# LED_bargraph.net
KiCad netlist of a schematic drawn in Altium Designer
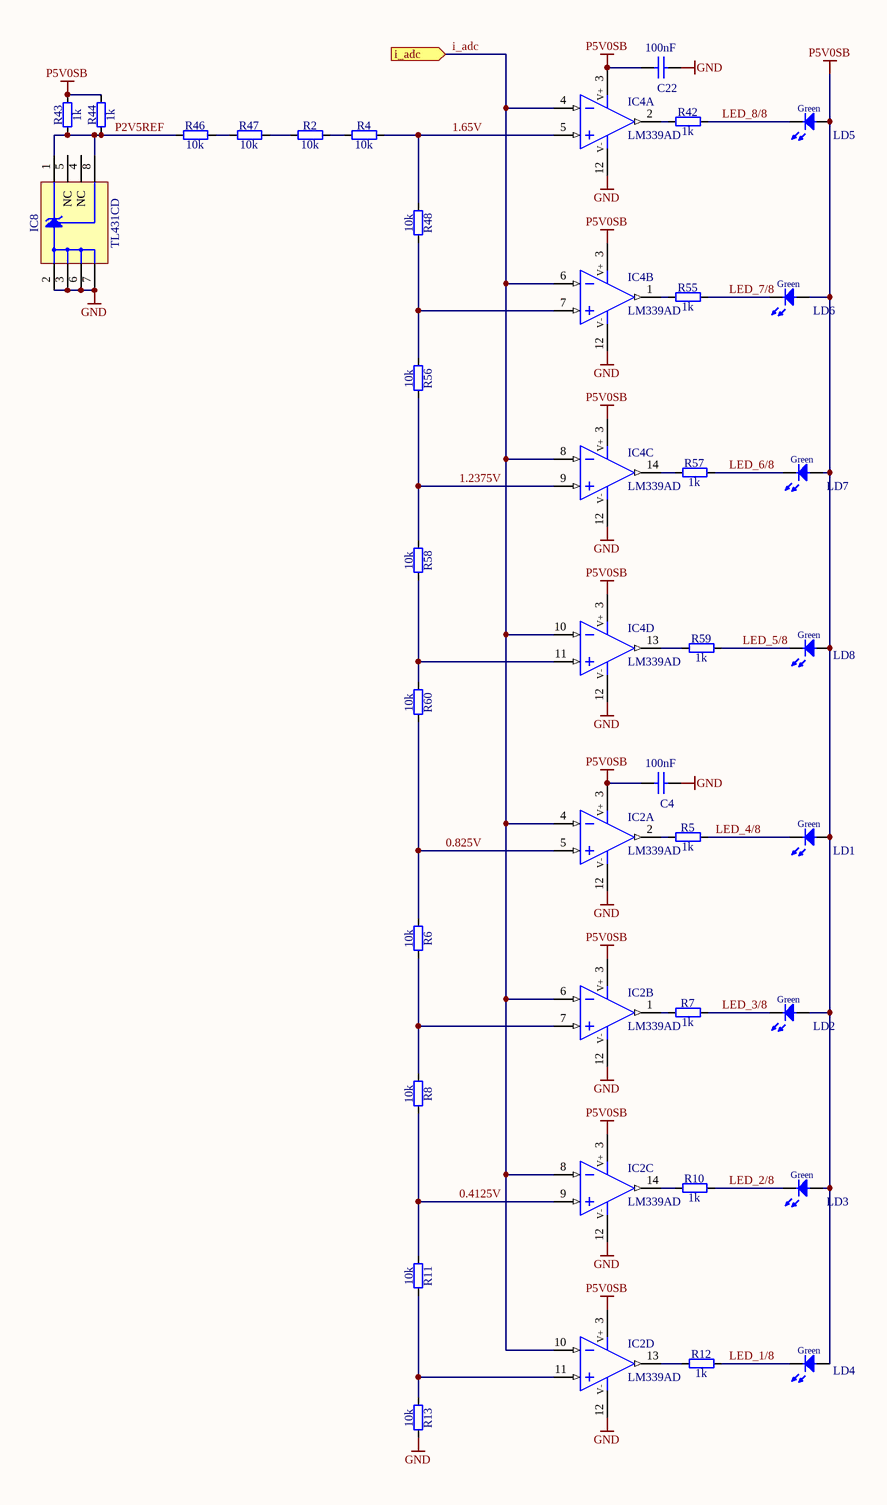
[diagram p0: LED_bargraph.SchDoc]

(export (version "E")
  (design (tool "Eeschema 10.0.6"))
  (components
    (comp (ref "C4")
      (value "100nF")
      (footprint "CAPC1005X55N")
      (description "Non-polarised capacitor")
      (fields
        (field (name "PART NUMBER") "CC0402_100NF_25V_10%_X7R_YUDEN_TMK105B7104KVHF")
        (field (name "VOLTAGE") "25V")
        (field (name "AUTHOR") "CERN DEM JLC")
      )
      (libsource (lib "Capacitors") (part "Capacitor - non polarized"))
    )
    (comp (ref "C22")
      (value "100nF")
      (footprint "CAPC1005X55N")
      (description "Non-polarised capacitor")
      (fields
        (field (name "PART NUMBER") "CC0402_100NF_25V_10%_X7R_YUDEN_TMK105B7104KVHF")
        (field (name "VOLTAGE") "25V")
        (field (name "AUTHOR") "CERN DEM JLC")
      )
      (libsource (lib "Capacitors") (part "Capacitor - non polarized"))
    )
    (comp (ref "IC2")
      (value "LM339AD")
      (footprint "SOIC127P600X175-14N")
      (description "Quad Operational Amplifier")
      (fields (field (name "MANUFACTURER") "TEXAS INSTRUMENTS") (field (name "AUTHOR") "CERN DEM JLC"))
      (libsource (lib "ICs And Semiconductors") (part "Operational Amplifier x4 Type2"))
    )
    (comp (ref "IC4")
      (value "LM339AD")
      (footprint "SOIC127P600X175-14N")
      (description "Quad Operational Amplifier")
      (fields (field (name "MANUFACTURER") "TEXAS INSTRUMENTS") (field (name "AUTHOR") "CERN DEM JLC"))
      (libsource (lib "ICs And Semiconductors") (part "Operational Amplifier x4 Type2"))
    )
    (comp (ref "IC8")
      (value "TL431CD")
      (footprint "SOIC127P600X175-8N")
      (description "Precision Programmable Reference")
      (fields (field (name "MANUFACTURER") "TEXAS INSTRUMENTS") (field (name "AUTHOR") "CERN DEM JLC"))
      (libsource (lib "ICs And Semiconductors") (part "TL431xD"))
    )
    (comp (ref "LD1")
      (value "Green")
      (footprint "LED_AVAGO_HSME-C120")
      (description "LED Green 1C 2A")
      (fields
        (field (name "PART NUMBER") "LED_AVAGO_HSME-C120")
        (field (name "MANUFACTURER") "AVAGO TECHNOLOGIES")
        (field (name "AUTHOR") "CERN DEM JMW")
      )
      (libsource (lib "ICs And Semiconductors") (part "LED Green 1C 2A"))
    )
    (comp (ref "LD2")
      (value "Green")
      (footprint "LED_AVAGO_HSME-C120")
      (description "LED Green 1C 2A")
      (fields
        (field (name "PART NUMBER") "LED_AVAGO_HSME-C120")
        (field (name "MANUFACTURER") "AVAGO TECHNOLOGIES")
        (field (name "AUTHOR") "CERN DEM JMW")
      )
      (libsource (lib "ICs And Semiconductors") (part "LED Green 1C 2A"))
    )
    (comp (ref "LD3")
      (value "Green")
      (footprint "LED_AVAGO_HSME-C120")
      (description "LED Green 1C 2A")
      (fields
        (field (name "PART NUMBER") "LED_AVAGO_HSME-C120")
        (field (name "MANUFACTURER") "AVAGO TECHNOLOGIES")
        (field (name "AUTHOR") "CERN DEM JMW")
      )
      (libsource (lib "ICs And Semiconductors") (part "LED Green 1C 2A"))
    )
    (comp (ref "LD4")
      (value "Green")
      (footprint "LED_AVAGO_HSME-C120")
      (description "LED Green 1C 2A")
      (fields
        (field (name "PART NUMBER") "LED_AVAGO_HSME-C120")
        (field (name "MANUFACTURER") "AVAGO TECHNOLOGIES")
        (field (name "AUTHOR") "CERN DEM JMW")
      )
      (libsource (lib "ICs And Semiconductors") (part "LED Green 1C 2A"))
    )
    (comp (ref "LD5")
      (value "Green")
      (footprint "LED_AVAGO_HSME-C120")
      (description "LED Green 1C 2A")
      (fields
        (field (name "PART NUMBER") "LED_AVAGO_HSME-C120")
        (field (name "MANUFACTURER") "AVAGO TECHNOLOGIES")
        (field (name "AUTHOR") "CERN DEM JMW")
      )
      (libsource (lib "ICs And Semiconductors") (part "LED Green 1C 2A"))
    )
    (comp (ref "LD6")
      (value "Green")
      (footprint "LED_AVAGO_HSME-C120")
      (description "LED Green 1C 2A")
      (fields
        (field (name "PART NUMBER") "LED_AVAGO_HSME-C120")
        (field (name "MANUFACTURER") "AVAGO TECHNOLOGIES")
        (field (name "AUTHOR") "CERN DEM JMW")
      )
      (libsource (lib "ICs And Semiconductors") (part "LED Green 1C 2A"))
    )
    (comp (ref "LD7")
      (value "Green")
      (footprint "LED_AVAGO_HSME-C120")
      (description "LED Green 1C 2A")
      (fields
        (field (name "PART NUMBER") "LED_AVAGO_HSME-C120")
        (field (name "MANUFACTURER") "AVAGO TECHNOLOGIES")
        (field (name "AUTHOR") "CERN DEM JMW")
      )
      (libsource (lib "ICs And Semiconductors") (part "LED Green 1C 2A"))
    )
    (comp (ref "LD8")
      (value "Green")
      (footprint "LED_AVAGO_HSME-C120")
      (description "LED Green 1C 2A")
      (fields
        (field (name "PART NUMBER") "LED_AVAGO_HSME-C120")
        (field (name "MANUFACTURER") "AVAGO TECHNOLOGIES")
        (field (name "AUTHOR") "CERN DEM JMW")
      )
      (libsource (lib "ICs And Semiconductors") (part "LED Green 1C 2A"))
    )
    (comp (ref "R2")
      (value "10k")
      (footprint "RESC1608X55N")
      (description "Resistor - 1%")
      (fields
        (field (name "PART NUMBER") "R0603_10K_1%_0.1W_100PPM")
        (field (name "POWER") "0.1W")
        (field (name "AUTHOR") "CERN DEM JLC")
      )
      (libsource (lib "Resistors") (part "Resistor - 1%"))
    )
    (comp (ref "R4")
      (value "10k")
      (footprint "RESC1608X55N")
      (description "Resistor - 1%")
      (fields
        (field (name "PART NUMBER") "R0603_10K_1%_0.1W_100PPM")
        (field (name "POWER") "0.1W")
        (field (name "AUTHOR") "CERN DEM JLC")
      )
      (libsource (lib "Resistors") (part "Resistor - 1%"))
    )
    (comp (ref "R5")
      (value "1k")
      (footprint "RESC1608X55N")
      (description "Resistor - 1%")
      (fields
        (field (name "PART NUMBER") "R0603_1K_1%_0.1W_100PPM")
        (field (name "POWER") "0.1W")
        (field (name "AUTHOR") "CERN DEM JLC")
      )
      (libsource (lib "Resistors") (part "Resistor - 1%"))
    )
    (comp (ref "R6")
      (value "10k")
      (footprint "RESC1608X55N")
      (description "Resistor - 1%")
      (fields
        (field (name "PART NUMBER") "R0603_10K_1%_0.1W_100PPM")
        (field (name "POWER") "0.1W")
        (field (name "AUTHOR") "CERN DEM JLC")
      )
      (libsource (lib "Resistors") (part "Resistor - 1%"))
    )
    (comp (ref "R7")
      (value "1k")
      (footprint "RESC1608X55N")
      (description "Resistor - 1%")
      (fields
        (field (name "PART NUMBER") "R0603_1K_1%_0.1W_100PPM")
        (field (name "POWER") "0.1W")
        (field (name "AUTHOR") "CERN DEM JLC")
      )
      (libsource (lib "Resistors") (part "Resistor - 1%"))
    )
    (comp (ref "R8")
      (value "10k")
      (footprint "RESC1608X55N")
      (description "Resistor - 1%")
      (fields
        (field (name "PART NUMBER") "R0603_10K_1%_0.1W_100PPM")
        (field (name "POWER") "0.1W")
        (field (name "AUTHOR") "CERN DEM JLC")
      )
      (libsource (lib "Resistors") (part "Resistor - 1%"))
    )
    (comp (ref "R10")
      (value "1k")
      (footprint "RESC1608X55N")
      (description "Resistor - 1%")
      (fields
        (field (name "PART NUMBER") "R0603_1K_1%_0.1W_100PPM")
        (field (name "POWER") "0.1W")
        (field (name "AUTHOR") "CERN DEM JLC")
      )
      (libsource (lib "Resistors") (part "Resistor - 1%"))
    )
    (comp (ref "R11")
      (value "10k")
      (footprint "RESC1608X55N")
      (description "Resistor - 1%")
      (fields
        (field (name "PART NUMBER") "R0603_10K_1%_0.1W_100PPM")
        (field (name "POWER") "0.1W")
        (field (name "AUTHOR") "CERN DEM JLC")
      )
      (libsource (lib "Resistors") (part "Resistor - 1%"))
    )
    (comp (ref "R12")
      (value "1k")
      (footprint "RESC1608X55N")
      (description "Resistor - 1%")
      (fields
        (field (name "PART NUMBER") "R0603_1K_1%_0.1W_100PPM")
        (field (name "POWER") "0.1W")
        (field (name "AUTHOR") "CERN DEM JLC")
      )
      (libsource (lib "Resistors") (part "Resistor - 1%"))
    )
    (comp (ref "R13")
      (value "10k")
      (footprint "RESC1608X55N")
      (description "Resistor - 1%")
      (fields
        (field (name "PART NUMBER") "R0603_10K_1%_0.1W_100PPM")
        (field (name "POWER") "0.1W")
        (field (name "AUTHOR") "CERN DEM JLC")
      )
      (libsource (lib "Resistors") (part "Resistor - 1%"))
    )
    (comp (ref "R42")
      (value "1k")
      (footprint "RESC1608X55N")
      (description "Resistor - 1%")
      (fields
        (field (name "PART NUMBER") "R0603_1K_1%_0.1W_100PPM")
        (field (name "POWER") "0.1W")
        (field (name "AUTHOR") "CERN DEM JLC")
      )
      (libsource (lib "Resistors") (part "Resistor - 1%"))
    )
    (comp (ref "R43")
      (value "1k")
      (footprint "RESC1608X55N")
      (description "Resistor - 1%")
      (fields
        (field (name "PART NUMBER") "R0603_1K_1%_0.1W_100PPM")
        (field (name "POWER") "0.1W")
        (field (name "AUTHOR") "CERN DEM JLC")
      )
      (libsource (lib "Resistors") (part "Resistor - 1%"))
    )
    (comp (ref "R44")
      (value "1k")
      (footprint "RESC1608X55N")
      (description "Resistor - 1%")
      (fields
        (field (name "PART NUMBER") "R0603_1K_1%_0.1W_100PPM")
        (field (name "POWER") "0.1W")
        (field (name "AUTHOR") "CERN DEM JLC")
      )
      (libsource (lib "Resistors") (part "Resistor - 1%"))
    )
    (comp (ref "R46")
      (value "10k")
      (footprint "RESC1608X55N")
      (description "Resistor - 1%")
      (fields
        (field (name "PART NUMBER") "R0603_10K_1%_0.1W_100PPM")
        (field (name "POWER") "0.1W")
        (field (name "AUTHOR") "CERN DEM JLC")
      )
      (libsource (lib "Resistors") (part "Resistor - 1%"))
    )
    (comp (ref "R47")
      (value "10k")
      (footprint "RESC1608X55N")
      (description "Resistor - 1%")
      (fields
        (field (name "PART NUMBER") "R0603_10K_1%_0.1W_100PPM")
        (field (name "POWER") "0.1W")
        (field (name "AUTHOR") "CERN DEM JLC")
      )
      (libsource (lib "Resistors") (part "Resistor - 1%"))
    )
    (comp (ref "R48")
      (value "10k")
      (footprint "RESC1608X55N")
      (description "Resistor - 1%")
      (fields
        (field (name "PART NUMBER") "R0603_10K_1%_0.1W_100PPM")
        (field (name "POWER") "0.1W")
        (field (name "AUTHOR") "CERN DEM JLC")
      )
      (libsource (lib "Resistors") (part "Resistor - 1%"))
    )
    (comp (ref "R55")
      (value "1k")
      (footprint "RESC1608X55N")
      (description "Resistor - 1%")
      (fields
        (field (name "PART NUMBER") "R0603_1K_1%_0.1W_100PPM")
        (field (name "POWER") "0.1W")
        (field (name "AUTHOR") "CERN DEM JLC")
      )
      (libsource (lib "Resistors") (part "Resistor - 1%"))
    )
    (comp (ref "R56")
      (value "10k")
      (footprint "RESC1608X55N")
      (description "Resistor - 1%")
      (fields
        (field (name "PART NUMBER") "R0603_10K_1%_0.1W_100PPM")
        (field (name "POWER") "0.1W")
        (field (name "AUTHOR") "CERN DEM JLC")
      )
      (libsource (lib "Resistors") (part "Resistor - 1%"))
    )
    (comp (ref "R57")
      (value "1k")
      (footprint "RESC1608X55N")
      (description "Resistor - 1%")
      (fields
        (field (name "PART NUMBER") "R0603_1K_1%_0.1W_100PPM")
        (field (name "POWER") "0.1W")
        (field (name "AUTHOR") "CERN DEM JLC")
      )
      (libsource (lib "Resistors") (part "Resistor - 1%"))
    )
    (comp (ref "R58")
      (value "10k")
      (footprint "RESC1608X55N")
      (description "Resistor - 1%")
      (fields
        (field (name "PART NUMBER") "R0603_10K_1%_0.1W_100PPM")
        (field (name "POWER") "0.1W")
        (field (name "AUTHOR") "CERN DEM JLC")
      )
      (libsource (lib "Resistors") (part "Resistor - 1%"))
    )
    (comp (ref "R59")
      (value "1k")
      (footprint "RESC1608X55N")
      (description "Resistor - 1%")
      (fields
        (field (name "PART NUMBER") "R0603_1K_1%_0.1W_100PPM")
        (field (name "POWER") "0.1W")
        (field (name "AUTHOR") "CERN DEM JLC")
      )
      (libsource (lib "Resistors") (part "Resistor - 1%"))
    )
    (comp (ref "R60")
      (value "10k")
      (footprint "RESC1608X55N")
      (description "Resistor - 1%")
      (fields
        (field (name "PART NUMBER") "R0603_10K_1%_0.1W_100PPM")
        (field (name "POWER") "0.1W")
        (field (name "AUTHOR") "CERN DEM JLC")
      )
      (libsource (lib "Resistors") (part "Resistor - 1%"))
    )
  )
  (nets
    (net (code "1") (name "/0.825V") (class "Default")
      (node (ref "IC2") (pin "5") (pinfunction "IN+_5") (pintype "input"))
      (node (ref "R6") (pin "1") (pinfunction "1_1") (pintype "passive"))
      (node (ref "R60") (pin "2") (pinfunction "2_2") (pintype "passive"))
    )
    (net (code "2") (name "/0.4125V") (class "Default")
      (node (ref "IC2") (pin "9") (pinfunction "IN+_9") (pintype "input"))
      (node (ref "R11") (pin "1") (pinfunction "1_1") (pintype "passive"))
      (node (ref "R8") (pin "2") (pinfunction "2_2") (pintype "passive"))
    )
    (net (code "3") (name "/1.65V") (class "Default")
      (node (ref "IC4") (pin "5") (pinfunction "IN+_5") (pintype "input"))
      (node (ref "R4") (pin "2") (pinfunction "2_2") (pintype "passive"))
      (node (ref "R48") (pin "1") (pinfunction "1_1") (pintype "passive"))
    )
    (net (code "4") (name "/1.2375V") (class "Default")
      (node (ref "IC4") (pin "9") (pinfunction "IN+_9") (pintype "input"))
      (node (ref "R56") (pin "2") (pinfunction "2_2") (pintype "passive"))
      (node (ref "R58") (pin "1") (pinfunction "1_1") (pintype "passive"))
    )
    (net (code "5") (name "/LED_1{slash}8") (class "Default")
      (node (ref "LD4") (pin "1") (pinfunction "C_1") (pintype "passive"))
      (node (ref "R12") (pin "2") (pinfunction "2_2") (pintype "passive"))
    )
    (net (code "6") (name "/LED_2{slash}8") (class "Default")
      (node (ref "LD3") (pin "1") (pinfunction "C_1") (pintype "passive"))
      (node (ref "R10") (pin "2") (pinfunction "2_2") (pintype "passive"))
    )
    (net (code "7") (name "/LED_3{slash}8") (class "Default")
      (node (ref "LD2") (pin "1") (pinfunction "C_1") (pintype "passive"))
      (node (ref "R7") (pin "2") (pinfunction "2_2") (pintype "passive"))
    )
    (net (code "8") (name "/LED_4{slash}8") (class "Default")
      (node (ref "LD1") (pin "1") (pinfunction "C_1") (pintype "passive"))
      (node (ref "R5") (pin "2") (pinfunction "2_2") (pintype "passive"))
    )
    (net (code "9") (name "/LED_5{slash}8") (class "Default")
      (node (ref "LD8") (pin "1") (pinfunction "C_1") (pintype "passive"))
      (node (ref "R59") (pin "2") (pinfunction "2_2") (pintype "passive"))
    )
    (net (code "10") (name "/LED_6{slash}8") (class "Default")
      (node (ref "LD7") (pin "1") (pinfunction "C_1") (pintype "passive"))
      (node (ref "R57") (pin "2") (pinfunction "2_2") (pintype "passive"))
    )
    (net (code "11") (name "/LED_7{slash}8") (class "Default")
      (node (ref "LD6") (pin "1") (pinfunction "C_1") (pintype "passive"))
      (node (ref "R55") (pin "2") (pinfunction "2_2") (pintype "passive"))
    )
    (net (code "12") (name "/LED_8{slash}8") (class "Default")
      (node (ref "LD5") (pin "1") (pinfunction "C_1") (pintype "passive"))
      (node (ref "R42") (pin "2") (pinfunction "2_2") (pintype "passive"))
    )
    (net (code "13") (name "/P2V5REF") (class "Default")
      (node (ref "IC8") (pin "1") (pinfunction "C_1") (pintype "passive"))
      (node (ref "IC8") (pin "8") (pinfunction "REF_8") (pintype "passive"))
      (node (ref "R43") (pin "1") (pinfunction "1_1") (pintype "passive"))
      (node (ref "R44") (pin "1") (pinfunction "1_1") (pintype "passive"))
      (node (ref "R46") (pin "1") (pinfunction "1_1") (pintype "passive"))
    )
    (net (code "14") (name "/i_adc") (class "Default")
      (node (ref "IC2") (pin "10") (pinfunction "IN-_10") (pintype "input"))
      (node (ref "IC2") (pin "4") (pinfunction "IN-_4") (pintype "input"))
      (node (ref "IC2") (pin "6") (pinfunction "IN-_6") (pintype "input"))
      (node (ref "IC2") (pin "8") (pinfunction "IN-_8") (pintype "input"))
      (node (ref "IC4") (pin "10") (pinfunction "IN-_10") (pintype "input"))
      (node (ref "IC4") (pin "4") (pinfunction "IN-_4") (pintype "input"))
      (node (ref "IC4") (pin "6") (pinfunction "IN-_6") (pintype "input"))
      (node (ref "IC4") (pin "8") (pinfunction "IN-_8") (pintype "input"))
    )
    (net (code "15") (name "GND") (class "Default")
      (node (ref "C22") (pin "1") (pinfunction "1_1") (pintype "passive"))
      (node (ref "C4") (pin "1") (pinfunction "1_1") (pintype "passive"))
      (node (ref "IC2") (pin "12") (pinfunction "V-_12") (pintype "power_in"))
      (node (ref "IC4") (pin "12") (pinfunction "V-_12") (pintype "power_in"))
      (node (ref "IC8") (pin "2") (pinfunction "A_2") (pintype "passive"))
      (node (ref "IC8") (pin "3") (pinfunction "A_3") (pintype "passive"))
      (node (ref "IC8") (pin "6") (pinfunction "A_6") (pintype "passive"))
      (node (ref "IC8") (pin "7") (pinfunction "A_7") (pintype "passive"))
      (node (ref "R13") (pin "2") (pinfunction "2_2") (pintype "passive"))
    )
    (net (code "16") (name "Net-(IC2A-OUT)") (class "Default")
      (node (ref "IC2") (pin "2") (pinfunction "OUT_2") (pintype "output"))
      (node (ref "R5") (pin "1") (pinfunction "1_1") (pintype "passive"))
    )
    (net (code "17") (name "Net-(IC2B-IN+)") (class "Default")
      (node (ref "IC2") (pin "7") (pinfunction "IN+_7") (pintype "input"))
      (node (ref "R6") (pin "2") (pinfunction "2_2") (pintype "passive"))
      (node (ref "R8") (pin "1") (pinfunction "1_1") (pintype "passive"))
    )
    (net (code "18") (name "Net-(IC2B-OUT)") (class "Default")
      (node (ref "IC2") (pin "1") (pinfunction "OUT_1") (pintype "output"))
      (node (ref "R7") (pin "1") (pinfunction "1_1") (pintype "passive"))
    )
    (net (code "19") (name "Net-(IC2C-OUT)") (class "Default")
      (node (ref "IC2") (pin "14") (pinfunction "OUT_14") (pintype "output"))
      (node (ref "R10") (pin "1") (pinfunction "1_1") (pintype "passive"))
    )
    (net (code "20") (name "Net-(IC2D-IN+)") (class "Default")
      (node (ref "IC2") (pin "11") (pinfunction "IN+_11") (pintype "input"))
      (node (ref "R11") (pin "2") (pinfunction "2_2") (pintype "passive"))
      (node (ref "R13") (pin "1") (pinfunction "1_1") (pintype "passive"))
    )
    (net (code "21") (name "Net-(IC2D-OUT)") (class "Default")
      (node (ref "IC2") (pin "13") (pinfunction "OUT_13") (pintype "output"))
      (node (ref "R12") (pin "1") (pinfunction "1_1") (pintype "passive"))
    )
    (net (code "22") (name "Net-(IC4A-OUT)") (class "Default")
      (node (ref "IC4") (pin "2") (pinfunction "OUT_2") (pintype "output"))
      (node (ref "R42") (pin "1") (pinfunction "1_1") (pintype "passive"))
    )
    (net (code "23") (name "Net-(IC4B-IN+)") (class "Default")
      (node (ref "IC4") (pin "7") (pinfunction "IN+_7") (pintype "input"))
      (node (ref "R48") (pin "2") (pinfunction "2_2") (pintype "passive"))
      (node (ref "R56") (pin "1") (pinfunction "1_1") (pintype "passive"))
    )
    (net (code "24") (name "Net-(IC4B-OUT)") (class "Default")
      (node (ref "IC4") (pin "1") (pinfunction "OUT_1") (pintype "output"))
      (node (ref "R55") (pin "1") (pinfunction "1_1") (pintype "passive"))
    )
    (net (code "25") (name "Net-(IC4C-OUT)") (class "Default")
      (node (ref "IC4") (pin "14") (pinfunction "OUT_14") (pintype "output"))
      (node (ref "R57") (pin "1") (pinfunction "1_1") (pintype "passive"))
    )
    (net (code "26") (name "Net-(IC4D-IN+)") (class "Default")
      (node (ref "IC4") (pin "11") (pinfunction "IN+_11") (pintype "input"))
      (node (ref "R58") (pin "2") (pinfunction "2_2") (pintype "passive"))
      (node (ref "R60") (pin "1") (pinfunction "1_1") (pintype "passive"))
    )
    (net (code "27") (name "Net-(IC4D-OUT)") (class "Default")
      (node (ref "IC4") (pin "13") (pinfunction "OUT_13") (pintype "output"))
      (node (ref "R59") (pin "1") (pinfunction "1_1") (pintype "passive"))
    )
    (net (code "28") (name "Net-(R2-Pad1)") (class "Default")
      (node (ref "R2") (pin "1") (pinfunction "1_1") (pintype "passive"))
      (node (ref "R47") (pin "2") (pinfunction "2_2") (pintype "passive"))
    )
    (net (code "29") (name "Net-(R2-Pad2)") (class "Default")
      (node (ref "R2") (pin "2") (pinfunction "2_2") (pintype "passive"))
      (node (ref "R4") (pin "1") (pinfunction "1_1") (pintype "passive"))
    )
    (net (code "30") (name "Net-(R46-Pad2)") (class "Default")
      (node (ref "R46") (pin "2") (pinfunction "2_2") (pintype "passive"))
      (node (ref "R47") (pin "1") (pinfunction "1_1") (pintype "passive"))
    )
    (net (code "31") (name "P5V0SB") (class "Default")
      (node (ref "C22") (pin "2") (pinfunction "2_2") (pintype "passive"))
      (node (ref "C4") (pin "2") (pinfunction "2_2") (pintype "passive"))
      (node (ref "IC2") (pin "3") (pinfunction "V+_3") (pintype "power_in"))
      (node (ref "IC4") (pin "3") (pinfunction "V+_3") (pintype "power_in"))
      (node (ref "LD1") (pin "2") (pinfunction "A_2") (pintype "passive"))
      (node (ref "LD2") (pin "2") (pinfunction "A_2") (pintype "passive"))
      (node (ref "LD3") (pin "2") (pinfunction "A_2") (pintype "passive"))
      (node (ref "LD4") (pin "2") (pinfunction "A_2") (pintype "passive"))
      (node (ref "LD5") (pin "2") (pinfunction "A_2") (pintype "passive"))
      (node (ref "LD6") (pin "2") (pinfunction "A_2") (pintype "passive"))
      (node (ref "LD7") (pin "2") (pinfunction "A_2") (pintype "passive"))
      (node (ref "LD8") (pin "2") (pinfunction "A_2") (pintype "passive"))
      (node (ref "R43") (pin "2") (pinfunction "2_2") (pintype "passive"))
      (node (ref "R44") (pin "2") (pinfunction "2_2") (pintype "passive"))
    )
    (net (code "32") (name "unconnected-(IC8-NC-Pad4)") (class "Default")
      (node (ref "IC8") (pin "4") (pinfunction "NC_4") (pintype "passive"))
    )
    (net (code "33") (name "unconnected-(IC8-NC-Pad5)") (class "Default")
      (node (ref "IC8") (pin "5") (pinfunction "NC_5") (pintype "passive"))
    )
  )
)
